# sch_cm4_pwr.net
KiCad netlist of a schematic drawn in Altium Designer
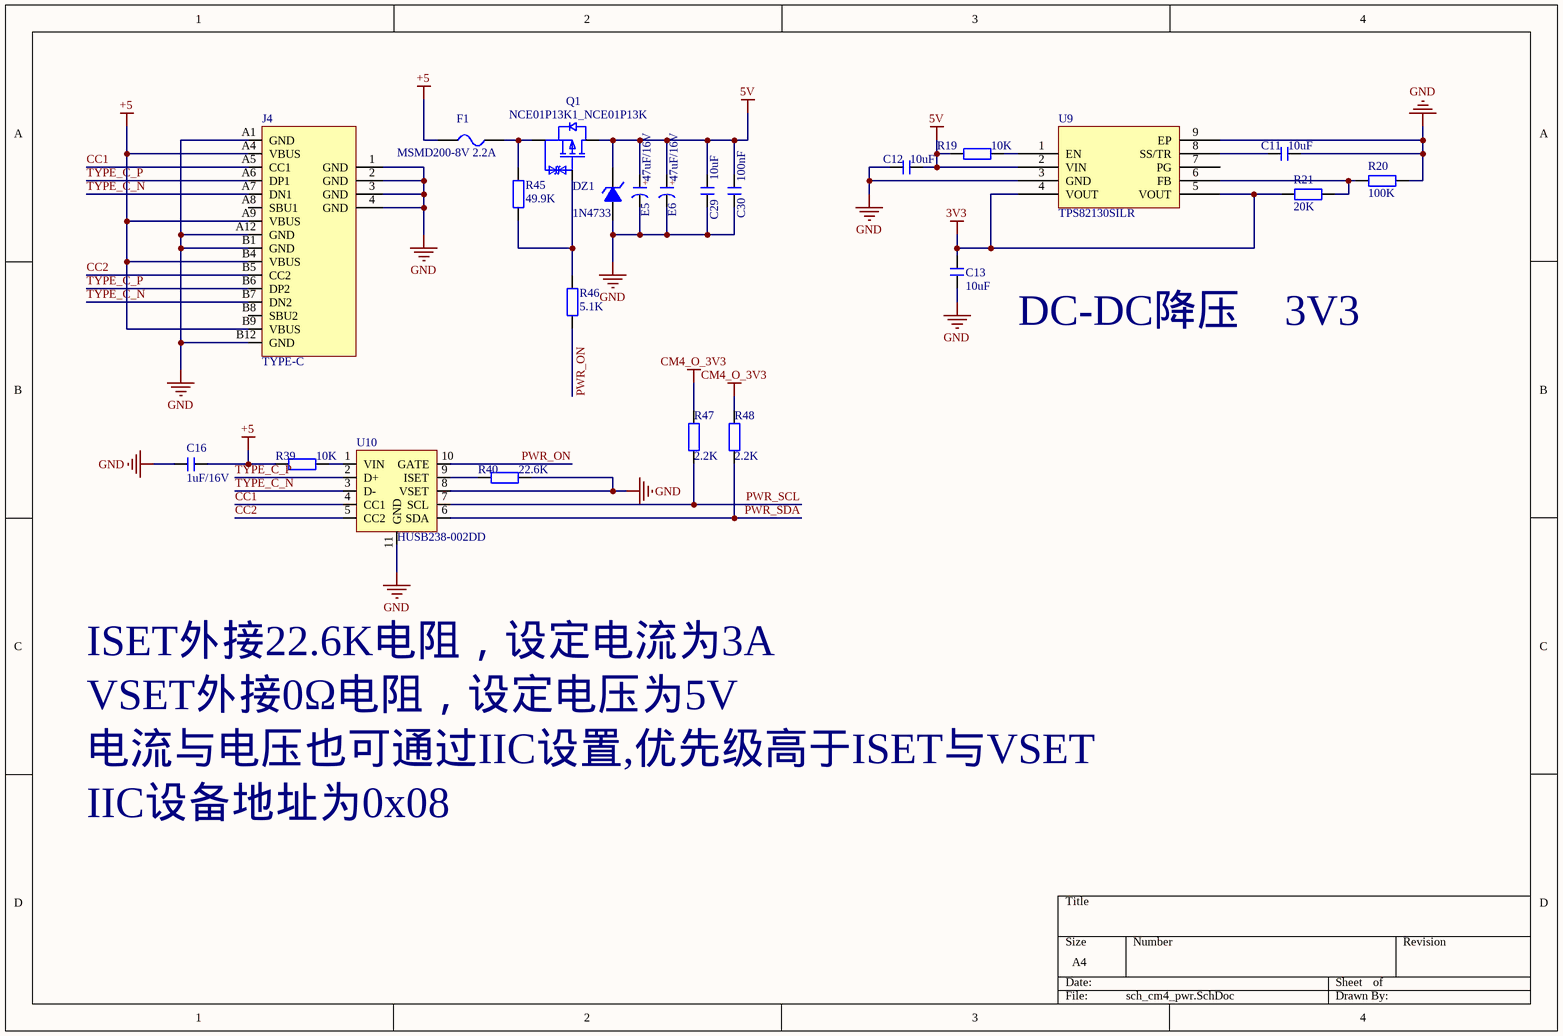
[diagram p0: sch_cm4_pwr.SchDoc]

(export (version "E")
  (design (tool "Eeschema 10.0.6"))
  (components
    (comp (ref "C11")
      (value "10uF")
      (footprint "C 0805_L")
      (description "贴片电容")
      (libsource (lib "0.1 - 电阻-电容-电感") (part "C"))
    )
    (comp (ref "C12")
      (value "10uF")
      (footprint "C 0805_L")
      (description "贴片电容")
      (libsource (lib "0.1 - 电阻-电容-电感") (part "C"))
    )
    (comp (ref "C13")
      (value "10uF")
      (footprint "C 0805_L")
      (description "贴片电容")
      (libsource (lib "0.1 - 电阻-电容-电感") (part "C"))
    )
    (comp (ref "C16")
      (value "1uF/16V")
      (footprint "C 0805_L")
      (description "贴片电容")
      (libsource (lib "0.1 - 电阻-电容-电感") (part "C"))
    )
    (comp (ref "C29")
      (value "10uF")
      (footprint "C 0805_L")
      (description "贴片电容")
      (libsource (lib "0.1 - 电阻-电容-电感") (part "C"))
    )
    (comp (ref "C30")
      (value "100nF")
      (footprint "C 0805_L")
      (description "贴片电容")
      (libsource (lib "0.1 - 电阻-电容-电感") (part "C"))
    )
    (comp (ref "DZ1")
      (value "1N4733")
      (footprint "SMA")
      (description "5.1V/1W稳压管")
      (fields (field (name "版权归属") "封装库来自淘宝 ID：黄晶宝石"))
      (libsource (lib "0.2 - 二极管-整流桥") (part "1N4733"))
    )
    (comp (ref "E5")
      (value "47uF/16V")
      (footprint "CD B(3528)")
      (description "贴片钽电容")
      (libsource (lib "0.1 - 电阻-电容-电感") (part "CT"))
    )
    (comp (ref "E6")
      (value "47uF/16V")
      (footprint "CD B(3528)")
      (description "贴片钽电容")
      (libsource (lib "0.1 - 电阻-电容-电感") (part "CT"))
    )
    (comp (ref "F1")
      (value "MSMD200-8V 2.2A")
      (footprint "FU 1812")
      (description "贴片保险丝")
      (fields (field (name "版权归属") "封装库来自淘宝卖家 ID：黄晶宝石"))
      (libsource (lib "2.0 - 保险丝-晶振-光耦") (part "FU"))
    )
    (comp (ref "J4")
      (value "TYPE-C")
      (footprint "TYPE-C USB3.1")
      (libsource (lib "schlib_cm4") (part "TYPE-C"))
    )
    (comp (ref "Q1")
      (value "NCE01P13K1_NCE01P13K")
      (footprint "TO-252-2_L6.6-W6.1-P4.57-LS10.1-TL-CW")
      (description "PMOS")
      (libsource (lib "schlib_cm4") (part "NCE01P13K1_NCE01P13K"))
    )
    (comp (ref "R19")
      (value "10K")
      (footprint "R 0805_L")
      (description "贴片电阻")
      (fields (field (name "版权归属") "来自淘宝 ID：黄晶宝石"))
      (libsource (lib "0.1 - 电阻-电容-电感") (part "R"))
    )
    (comp (ref "R20")
      (value "100K")
      (footprint "R 0805_L")
      (description "贴片电阻")
      (fields (field (name "版权归属") "来自淘宝 ID：黄晶宝石"))
      (libsource (lib "0.1 - 电阻-电容-电感") (part "R"))
    )
    (comp (ref "R21")
      (value "20K")
      (footprint "R 0805_L")
      (description "贴片电阻")
      (fields (field (name "版权归属") "来自淘宝 ID：黄晶宝石"))
      (libsource (lib "0.1 - 电阻-电容-电感") (part "R"))
    )
    (comp (ref "R39")
      (value "10K")
      (footprint "R 0805_L")
      (description "贴片电阻")
      (fields (field (name "版权归属") "来自淘宝 ID：黄晶宝石"))
      (libsource (lib "0.1 - 电阻-电容-电感") (part "R"))
    )
    (comp (ref "R40")
      (value "22.6K")
      (footprint "R 0805_L")
      (description "贴片电阻")
      (fields (field (name "版权归属") "来自淘宝 ID：黄晶宝石"))
      (libsource (lib "0.1 - 电阻-电容-电感") (part "R"))
    )
    (comp (ref "R45")
      (value "49.9K")
      (footprint "R 0805_L")
      (description "贴片电阻")
      (fields (field (name "版权归属") "来自淘宝 ID：黄晶宝石"))
      (libsource (lib "0.1 - 电阻-电容-电感") (part "R"))
    )
    (comp (ref "R46")
      (value "5.1K")
      (footprint "R 0805_L")
      (description "贴片电阻")
      (fields (field (name "版权归属") "来自淘宝 ID：黄晶宝石"))
      (libsource (lib "0.1 - 电阻-电容-电感") (part "R"))
    )
    (comp (ref "R47")
      (value "2.2K")
      (footprint "R 0805_L")
      (description "贴片电阻")
      (fields (field (name "版权归属") "来自淘宝 ID：黄晶宝石"))
      (libsource (lib "0.1 - 电阻-电容-电感") (part "R"))
    )
    (comp (ref "R48")
      (value "2.2K")
      (footprint "R 0805_L")
      (description "贴片电阻")
      (fields (field (name "版权归属") "来自淘宝 ID：黄晶宝石"))
      (libsource (lib "0.1 - 电阻-电容-电感") (part "R"))
    )
    (comp (ref "U9")
      (value "TPS82130SILR")
      (footprint "TPS82130SILR")
      (description "DC-DC")
      (libsource (lib "schlib_substrate") (part "TPS82130SILR"))
    )
    (comp (ref "U10")
      (value "HUSB238-002DD")
      (footprint "DFN-10_L3.0-W3.0-P0.50-BL-EP2.5")
      (description "IC")
      (libsource (lib "schlib_cm4") (part "HSB38_002DD"))
    )
  )
  (nets
    (net (code "1") (name "+5") (class "Default")
      (node (ref "C16") (pin "1") (pinfunction "1_1") (pintype "passive"))
      (node (ref "F1") (pin "1") (pinfunction "1_1") (pintype "passive"))
      (node (ref "J4") (pin "A4") (pinfunction "VBUS_A4") (pintype "passive"))
      (node (ref "J4") (pin "A9") (pinfunction "VBUS_A9") (pintype "passive"))
      (node (ref "J4") (pin "B4") (pinfunction "VBUS_B4") (pintype "passive"))
      (node (ref "J4") (pin "B9") (pinfunction "VBUS_B9") (pintype "passive"))
      (node (ref "R39") (pin "1") (pinfunction "1_1") (pintype "passive"))
    )
    (net (code "2") (name "/CC1") (class "Default")
      (node (ref "J4") (pin "A5") (pinfunction "CC1_A5") (pintype "passive"))
      (node (ref "U10") (pin "4") (pinfunction "CC1_4") (pintype "passive"))
    )
    (net (code "3") (name "/CC2") (class "Default")
      (node (ref "J4") (pin "B5") (pinfunction "CC2_B5") (pintype "passive"))
      (node (ref "U10") (pin "5") (pinfunction "CC2_5") (pintype "passive"))
    )
    (net (code "4") (name "/PWR_ON") (class "Default")
      (node (ref "R46") (pin "1") (pinfunction "1_1") (pintype "passive"))
      (node (ref "U10") (pin "10") (pinfunction "GATE_10") (pintype "passive"))
    )
    (net (code "5") (name "/PWR_SCL") (class "Default")
      (node (ref "R47") (pin "1") (pinfunction "1_1") (pintype "passive"))
      (node (ref "U10") (pin "7") (pinfunction "SCL_7") (pintype "passive"))
    )
    (net (code "6") (name "/PWR_SDA") (class "Default")
      (node (ref "R48") (pin "1") (pinfunction "1_1") (pintype "passive"))
      (node (ref "U10") (pin "6") (pinfunction "SDA_6") (pintype "passive"))
    )
    (net (code "7") (name "/TYPE_C_N") (class "Default")
      (node (ref "J4") (pin "A7") (pinfunction "DN1_A7") (pintype "passive"))
      (node (ref "J4") (pin "B7") (pinfunction "DN2_B7") (pintype "passive"))
      (node (ref "U10") (pin "3") (pinfunction "D-_3") (pintype "passive"))
    )
    (net (code "8") (name "/TYPE_C_P") (class "Default")
      (node (ref "J4") (pin "A6") (pinfunction "DP1_A6") (pintype "passive"))
      (node (ref "J4") (pin "B6") (pinfunction "DP2_B6") (pintype "passive"))
      (node (ref "U10") (pin "2") (pinfunction "D+_2") (pintype "passive"))
    )
    (net (code "9") (name "3V3") (class "Default")
      (node (ref "C13") (pin "2") (pinfunction "2_2") (pintype "passive"))
      (node (ref "R21") (pin "1") (pinfunction "1_1") (pintype "passive"))
      (node (ref "U9") (pin "4") (pinfunction "VOUT_4") (pintype "passive"))
      (node (ref "U9") (pin "5") (pinfunction "VOUT_5") (pintype "passive"))
    )
    (net (code "10") (name "5V") (class "Default")
      (node (ref "C12") (pin "2") (pinfunction "2_2") (pintype "passive"))
      (node (ref "C29") (pin "2") (pinfunction "2_2") (pintype "passive"))
      (node (ref "C30") (pin "2") (pinfunction "2_2") (pintype "passive"))
      (node (ref "DZ1") (pin "2") (pinfunction "K_2") (pintype "passive"))
      (node (ref "E5") (pin "1") (pinfunction "A_1") (pintype "passive"))
      (node (ref "E6") (pin "1") (pinfunction "A_1") (pintype "passive"))
      (node (ref "Q1") (pin "2") (pinfunction "D_2") (pintype "passive"))
      (node (ref "R19") (pin "1") (pinfunction "1_1") (pintype "passive"))
      (node (ref "U9") (pin "2") (pinfunction "VIN_2") (pintype "passive"))
    )
    (net (code "11") (name "CM4_O_3V3") (class "Default")
      (node (ref "R47") (pin "2") (pinfunction "2_2") (pintype "passive"))
      (node (ref "R48") (pin "2") (pinfunction "2_2") (pintype "passive"))
    )
    (net (code "12") (name "GND") (class "Default")
      (node (ref "C11") (pin "2") (pinfunction "2_2") (pintype "passive"))
      (node (ref "C12") (pin "1") (pinfunction "1_1") (pintype "passive"))
      (node (ref "C13") (pin "1") (pinfunction "1_1") (pintype "passive"))
      (node (ref "C16") (pin "2") (pinfunction "2_2") (pintype "passive"))
      (node (ref "C29") (pin "1") (pinfunction "1_1") (pintype "passive"))
      (node (ref "C30") (pin "1") (pinfunction "1_1") (pintype "passive"))
      (node (ref "DZ1") (pin "1") (pinfunction "A_1") (pintype "passive"))
      (node (ref "E5") (pin "2") (pinfunction "K_2") (pintype "passive"))
      (node (ref "E6") (pin "2") (pinfunction "K_2") (pintype "passive"))
      (node (ref "J4") (pin "1") (pinfunction "GND_1") (pintype "passive"))
      (node (ref "J4") (pin "2") (pinfunction "GND_2") (pintype "passive"))
      (node (ref "J4") (pin "3") (pinfunction "GND_3") (pintype "passive"))
      (node (ref "J4") (pin "4") (pinfunction "GND_4") (pintype "passive"))
      (node (ref "J4") (pin "A1") (pinfunction "GND_A1") (pintype "passive"))
      (node (ref "J4") (pin "A12") (pinfunction "GND_A12") (pintype "passive"))
      (node (ref "J4") (pin "B1") (pinfunction "GND_B1") (pintype "passive"))
      (node (ref "J4") (pin "B12") (pinfunction "GND_B12") (pintype "passive"))
      (node (ref "R20") (pin "2") (pinfunction "2_2") (pintype "passive"))
      (node (ref "R40") (pin "2") (pinfunction "2_2") (pintype "passive"))
      (node (ref "U10") (pin "11") (pinfunction "GND_11") (pintype "passive"))
      (node (ref "U10") (pin "8") (pinfunction "VSET_8") (pintype "passive"))
      (node (ref "U9") (pin "3") (pinfunction "GND_3") (pintype "passive"))
      (node (ref "U9") (pin "9") (pinfunction "EP_9") (pintype "passive"))
    )
    (net (code "13") (name "Net-(Q1-G)") (class "Default")
      (node (ref "Q1") (pin "1") (pinfunction "G_1") (pintype "passive"))
      (node (ref "R45") (pin "1") (pinfunction "1_1") (pintype "passive"))
      (node (ref "R46") (pin "2") (pinfunction "2_2") (pintype "passive"))
    )
    (net (code "14") (name "Net-(Q1-S)") (class "Default")
      (node (ref "F1") (pin "2") (pinfunction "2_2") (pintype "passive"))
      (node (ref "Q1") (pin "3") (pinfunction "S_3") (pintype "passive"))
      (node (ref "R45") (pin "2") (pinfunction "2_2") (pintype "passive"))
    )
    (net (code "15") (name "Net-(U9-EN)") (class "Default")
      (node (ref "R19") (pin "2") (pinfunction "2_2") (pintype "passive"))
      (node (ref "U9") (pin "1") (pinfunction "EN_1") (pintype "passive"))
    )
    (net (code "16") (name "Net-(U9-FB)") (class "Default")
      (node (ref "R20") (pin "1") (pinfunction "1_1") (pintype "passive"))
      (node (ref "R21") (pin "2") (pinfunction "2_2") (pintype "passive"))
      (node (ref "U9") (pin "6") (pinfunction "FB_6") (pintype "passive"))
    )
    (net (code "17") (name "Net-(U9-SS{slash}TR)") (class "Default")
      (node (ref "C11") (pin "1") (pinfunction "1_1") (pintype "passive"))
      (node (ref "U9") (pin "8") (pinfunction "SS/TR_8") (pintype "passive"))
    )
    (net (code "18") (name "Net-(U10-ISET)") (class "Default")
      (node (ref "R40") (pin "1") (pinfunction "1_1") (pintype "passive"))
      (node (ref "U10") (pin "9") (pinfunction "ISET_9") (pintype "passive"))
    )
    (net (code "19") (name "Net-(U10-VIN)") (class "Default")
      (node (ref "R39") (pin "2") (pinfunction "2_2") (pintype "passive"))
      (node (ref "U10") (pin "1") (pinfunction "VIN_1") (pintype "passive"))
    )
    (net (code "20") (name "unconnected-(J4-SBU1-PadA8)") (class "Default")
      (node (ref "J4") (pin "A8") (pinfunction "SBU1_A8") (pintype "passive"))
    )
    (net (code "21") (name "unconnected-(J4-SBU2-PadB8)") (class "Default")
      (node (ref "J4") (pin "B8") (pinfunction "SBU2_B8") (pintype "passive"))
    )
    (net (code "22") (name "unconnected-(U9-PG-Pad7)") (class "Default")
      (node (ref "U9") (pin "7") (pinfunction "PG_7") (pintype "passive"))
    )
  )
)
